# LEDs.net
KiCad netlist of a schematic drawn in Altium Designer
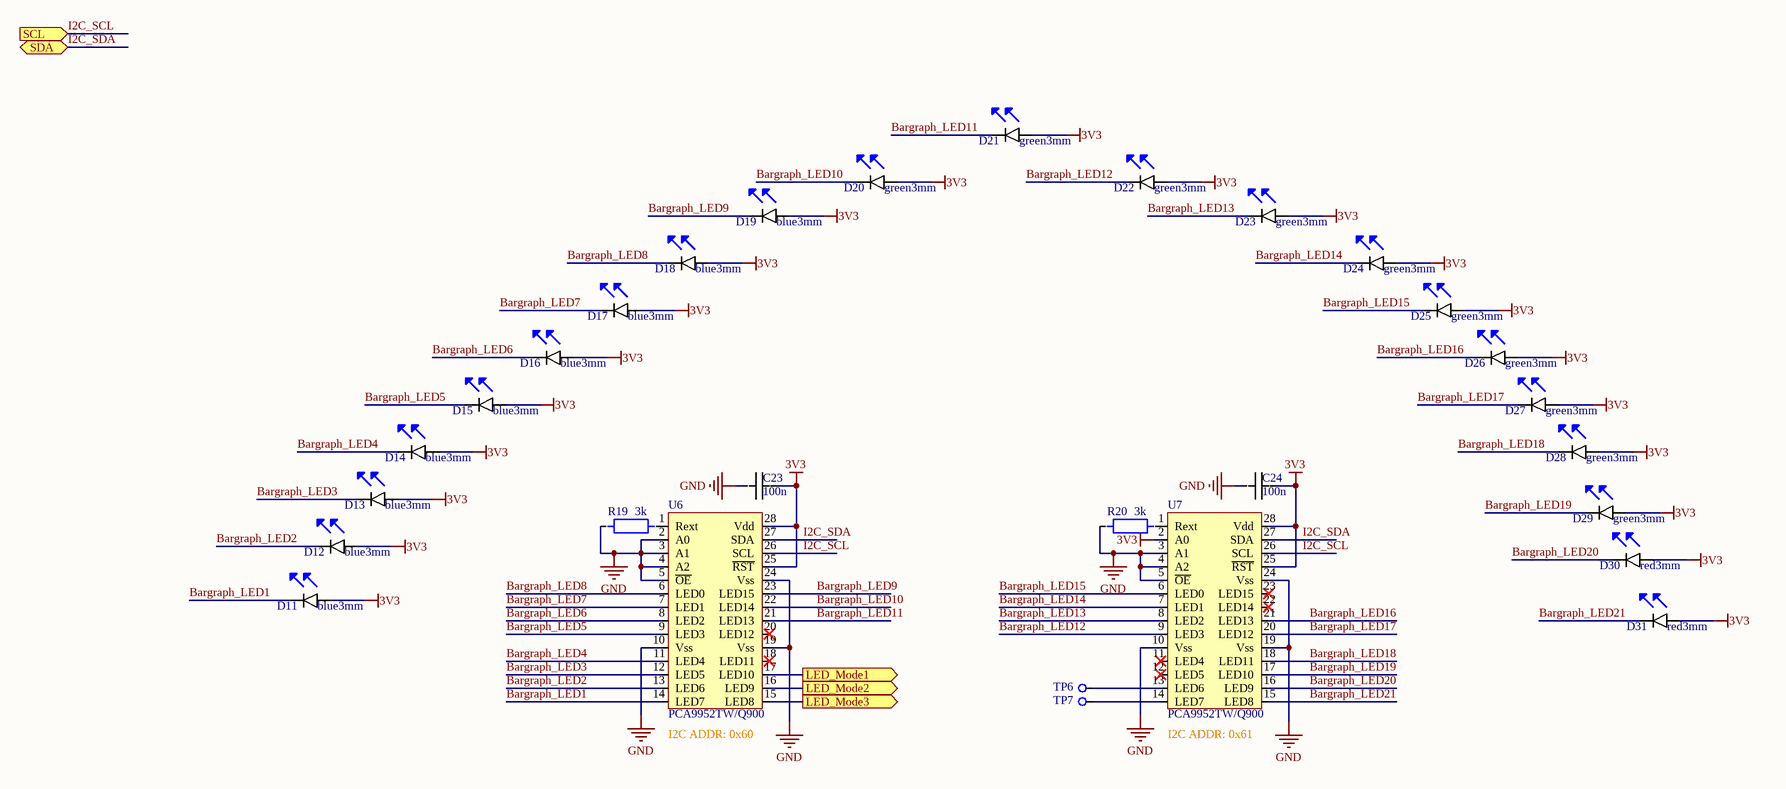
[diagram p0: LEDs.SchDoc]

(export (version "E")
  (design (tool "Eeschema 10.0.6"))
  (components
    (comp (ref "C23")
      (value "100n")
      (footprint "0402_")
      (fields
        (field (name "MANUFACTURER PARTNUM") "C1005X5R1E104K050BC")
        (field (name "MANUFACTURER") "TDK Corp")
      )
      (libsource (lib "*") (part "C"))
    )
    (comp (ref "C24")
      (value "100n")
      (footprint "0402_")
      (fields
        (field (name "MANUFACTURER PARTNUM") "C1005X5R1E104K050BC")
        (field (name "MANUFACTURER") "TDK Corp")
      )
      (libsource (lib "*") (part "C"))
    )
    (comp (ref "D11")
      (value "led")
      (footprint "LED3MM_BLUE")
      (fields
        (field (name "MANUFACTURER") "Wuerth")
        (field (name "MANUFACTURER PARTNUM") "151033BS03000")
        (field (name "COLOR_DIAM") "blue3mm")
      )
      (libsource (lib "*") (part "led"))
    )
    (comp (ref "D12")
      (value "led")
      (footprint "LED3MM_BLUE")
      (fields
        (field (name "MANUFACTURER") "Wuerth")
        (field (name "MANUFACTURER PARTNUM") "151033BS03000")
        (field (name "COLOR_DIAM") "blue3mm")
      )
      (libsource (lib "*") (part "led"))
    )
    (comp (ref "D13")
      (value "led")
      (footprint "LED3MM_BLUE")
      (fields
        (field (name "MANUFACTURER") "Wuerth")
        (field (name "MANUFACTURER PARTNUM") "151033BS03000")
        (field (name "COLOR_DIAM") "blue3mm")
      )
      (libsource (lib "*") (part "led"))
    )
    (comp (ref "D14")
      (value "led")
      (footprint "LED3MM_BLUE")
      (fields
        (field (name "MANUFACTURER") "Wuerth")
        (field (name "MANUFACTURER PARTNUM") "151033BS03000")
        (field (name "COLOR_DIAM") "blue3mm")
      )
      (libsource (lib "*") (part "led"))
    )
    (comp (ref "D15")
      (value "led")
      (footprint "LED3MM_BLUE")
      (fields
        (field (name "MANUFACTURER") "Wuerth")
        (field (name "MANUFACTURER PARTNUM") "151033BS03000")
        (field (name "COLOR_DIAM") "blue3mm")
      )
      (libsource (lib "*") (part "led"))
    )
    (comp (ref "D16")
      (value "led")
      (footprint "LED3MM_BLUE")
      (fields
        (field (name "MANUFACTURER") "Wuerth")
        (field (name "MANUFACTURER PARTNUM") "151033BS03000")
        (field (name "COLOR_DIAM") "blue3mm")
      )
      (libsource (lib "*") (part "led"))
    )
    (comp (ref "D17")
      (value "led")
      (footprint "LED3MM_BLUE")
      (fields
        (field (name "MANUFACTURER") "Wuerth")
        (field (name "MANUFACTURER PARTNUM") "151033BS03000")
        (field (name "COLOR_DIAM") "blue3mm")
      )
      (libsource (lib "*") (part "led"))
    )
    (comp (ref "D18")
      (value "led")
      (footprint "LED3MM_BLUE")
      (fields
        (field (name "MANUFACTURER") "Wuerth")
        (field (name "MANUFACTURER PARTNUM") "151033BS03000")
        (field (name "COLOR_DIAM") "blue3mm")
      )
      (libsource (lib "*") (part "led"))
    )
    (comp (ref "D19")
      (value "led")
      (footprint "LED3MM_BLUE")
      (fields
        (field (name "MANUFACTURER") "Wuerth")
        (field (name "MANUFACTURER PARTNUM") "151033BS03000")
        (field (name "COLOR_DIAM") "blue3mm")
      )
      (libsource (lib "*") (part "led"))
    )
    (comp (ref "D20")
      (value "led")
      (footprint "LED3MM_GREEN")
      (fields
        (field (name "MANUFACTURER") "Kingbright")
        (field (name "MANUFACTURER PARTNUM") "WP710A10LZGCK")
        (field (name "COLOR_DIAM") "green3mm")
      )
      (libsource (lib "*") (part "led"))
    )
    (comp (ref "D21")
      (value "led")
      (footprint "LED3MM_GREEN")
      (fields
        (field (name "MANUFACTURER") "Kingbright")
        (field (name "MANUFACTURER PARTNUM") "WP710A10LZGCK")
        (field (name "COLOR_DIAM") "green3mm")
      )
      (libsource (lib "*") (part "led"))
    )
    (comp (ref "D22")
      (value "led")
      (footprint "LED3MM_GREEN")
      (fields
        (field (name "MANUFACTURER") "Kingbright")
        (field (name "MANUFACTURER PARTNUM") "WP710A10LZGCK")
        (field (name "COLOR_DIAM") "green3mm")
      )
      (libsource (lib "*") (part "led"))
    )
    (comp (ref "D23")
      (value "led")
      (footprint "LED3MM_GREEN")
      (fields
        (field (name "MANUFACTURER") "Kingbright")
        (field (name "MANUFACTURER PARTNUM") "WP710A10LZGCK")
        (field (name "COLOR_DIAM") "green3mm")
      )
      (libsource (lib "*") (part "led"))
    )
    (comp (ref "D24")
      (value "led")
      (footprint "LED3MM_GREEN")
      (fields
        (field (name "MANUFACTURER") "Kingbright")
        (field (name "MANUFACTURER PARTNUM") "WP710A10LZGCK")
        (field (name "COLOR_DIAM") "green3mm")
      )
      (libsource (lib "*") (part "led"))
    )
    (comp (ref "D25")
      (value "led")
      (footprint "LED3MM_GREEN")
      (fields
        (field (name "MANUFACTURER") "Kingbright")
        (field (name "MANUFACTURER PARTNUM") "WP710A10LZGCK")
        (field (name "COLOR_DIAM") "green3mm")
      )
      (libsource (lib "*") (part "led"))
    )
    (comp (ref "D26")
      (value "led")
      (footprint "LED3MM_GREEN")
      (fields
        (field (name "MANUFACTURER") "Kingbright")
        (field (name "MANUFACTURER PARTNUM") "WP710A10LZGCK")
        (field (name "COLOR_DIAM") "green3mm")
      )
      (libsource (lib "*") (part "led"))
    )
    (comp (ref "D27")
      (value "led")
      (footprint "LED3MM_GREEN")
      (fields
        (field (name "MANUFACTURER") "Kingbright")
        (field (name "MANUFACTURER PARTNUM") "WP710A10LZGCK")
        (field (name "COLOR_DIAM") "green3mm")
      )
      (libsource (lib "*") (part "led"))
    )
    (comp (ref "D28")
      (value "led")
      (footprint "LED3MM_GREEN")
      (fields
        (field (name "MANUFACTURER") "Kingbright")
        (field (name "MANUFACTURER PARTNUM") "WP710A10LZGCK")
        (field (name "COLOR_DIAM") "green3mm")
      )
      (libsource (lib "*") (part "led"))
    )
    (comp (ref "D29")
      (value "led")
      (footprint "LED3MM_GREEN")
      (fields
        (field (name "MANUFACTURER") "Kingbright")
        (field (name "MANUFACTURER PARTNUM") "WP710A10LZGCK")
        (field (name "COLOR_DIAM") "green3mm")
      )
      (libsource (lib "*") (part "led"))
    )
    (comp (ref "D30")
      (value "led")
      (footprint "LED3MM_RED")
      (fields
        (field (name "MANUFACTURER") "Wuerth")
        (field (name "MANUFACTURER PARTNUM") "151033RS03000")
        (field (name "COLOR_DIAM") "red3mm")
      )
      (libsource (lib "*") (part "led"))
    )
    (comp (ref "D31")
      (value "led")
      (footprint "LED3MM_RED")
      (fields
        (field (name "MANUFACTURER") "Wuerth")
        (field (name "MANUFACTURER PARTNUM") "151033RS03000")
        (field (name "COLOR_DIAM") "red3mm")
      )
      (libsource (lib "*") (part "led"))
    )
    (comp (ref "R19")
      (value "3k")
      (footprint "0402_")
      (fields (field (name "MANUFACTURER PARTNUM") "RC0402FR-073KL") (field (name "MANUFACTURER") "Yageo"))
      (libsource (lib "*") (part "R"))
    )
    (comp (ref "R20")
      (value "3k")
      (footprint "0402_")
      (fields (field (name "MANUFACTURER PARTNUM") "RC0402FR-073KL") (field (name "MANUFACTURER") "Yageo"))
      (libsource (lib "*") (part "R"))
    )
    (comp (ref "TP6") (value "TP") (footprint "TP_PogoPin") (libsource (lib "Sch_GB_lib") (part "TP")))
    (comp (ref "TP7") (value "TP") (footprint "TP_PogoPin") (libsource (lib "Sch_GB_lib") (part "TP")))
    (comp (ref "U6")
      (value "PCA9952TW/Q900")
      (footprint "HTSSOP28")
      (fields (field (name "MANUFACTURER") "NXP") (field (name "MANUFACTURER PARTNUM") "PCA9952TW/Q900,118"))
      (libsource (lib "Sch_GB_lib") (part "PCA9952TW/Q900"))
    )
    (comp (ref "U7")
      (value "PCA9952TW/Q900")
      (footprint "HTSSOP28")
      (fields (field (name "MANUFACTURER") "NXP") (field (name "MANUFACTURER PARTNUM") "PCA9952TW/Q900,118"))
      (libsource (lib "Sch_GB_lib") (part "PCA9952TW/Q900"))
    )
  )
  (nets
    (net (code "1") (name "/Bargraph_LED1") (class "Default")
      (node (ref "D11") (pin "2") (pinfunction "2_2") (pintype "passive"))
      (node (ref "U6") (pin "14") (pinfunction "LED7_14") (pintype "passive"))
    )
    (net (code "2") (name "/Bargraph_LED2") (class "Default")
      (node (ref "D12") (pin "2") (pinfunction "2_2") (pintype "passive"))
      (node (ref "U6") (pin "13") (pinfunction "LED6_13") (pintype "passive"))
    )
    (net (code "3") (name "/Bargraph_LED3") (class "Default")
      (node (ref "D13") (pin "2") (pinfunction "2_2") (pintype "passive"))
      (node (ref "U6") (pin "12") (pinfunction "LED5_12") (pintype "passive"))
    )
    (net (code "4") (name "/Bargraph_LED4") (class "Default")
      (node (ref "D14") (pin "2") (pinfunction "2_2") (pintype "passive"))
      (node (ref "U6") (pin "11") (pinfunction "LED4_11") (pintype "passive"))
    )
    (net (code "5") (name "/Bargraph_LED5") (class "Default")
      (node (ref "D15") (pin "2") (pinfunction "2_2") (pintype "passive"))
      (node (ref "U6") (pin "9") (pinfunction "LED3_9") (pintype "passive"))
    )
    (net (code "6") (name "/Bargraph_LED6") (class "Default")
      (node (ref "D16") (pin "2") (pinfunction "2_2") (pintype "passive"))
      (node (ref "U6") (pin "8") (pinfunction "LED2_8") (pintype "passive"))
    )
    (net (code "7") (name "/Bargraph_LED7") (class "Default")
      (node (ref "D17") (pin "2") (pinfunction "2_2") (pintype "passive"))
      (node (ref "U6") (pin "7") (pinfunction "LED1_7") (pintype "passive"))
    )
    (net (code "8") (name "/Bargraph_LED8") (class "Default")
      (node (ref "D18") (pin "2") (pinfunction "2_2") (pintype "passive"))
      (node (ref "U6") (pin "6") (pinfunction "LED0_6") (pintype "passive"))
    )
    (net (code "9") (name "/Bargraph_LED9") (class "Default")
      (node (ref "D19") (pin "2") (pinfunction "2_2") (pintype "passive"))
      (node (ref "U6") (pin "23") (pinfunction "LED15_23") (pintype "passive"))
    )
    (net (code "10") (name "/Bargraph_LED10") (class "Default")
      (node (ref "D20") (pin "2") (pinfunction "2_2") (pintype "passive"))
      (node (ref "U6") (pin "22") (pinfunction "LED14_22") (pintype "passive"))
    )
    (net (code "11") (name "/Bargraph_LED11") (class "Default")
      (node (ref "D21") (pin "2") (pinfunction "2_2") (pintype "passive"))
      (node (ref "U6") (pin "21") (pinfunction "LED13_21") (pintype "passive"))
    )
    (net (code "12") (name "/Bargraph_LED12") (class "Default")
      (node (ref "D22") (pin "2") (pinfunction "2_2") (pintype "passive"))
      (node (ref "U7") (pin "9") (pinfunction "LED3_9") (pintype "passive"))
    )
    (net (code "13") (name "/Bargraph_LED13") (class "Default")
      (node (ref "D23") (pin "2") (pinfunction "2_2") (pintype "passive"))
      (node (ref "U7") (pin "8") (pinfunction "LED2_8") (pintype "passive"))
    )
    (net (code "14") (name "/Bargraph_LED14") (class "Default")
      (node (ref "D24") (pin "2") (pinfunction "2_2") (pintype "passive"))
      (node (ref "U7") (pin "7") (pinfunction "LED1_7") (pintype "passive"))
    )
    (net (code "15") (name "/Bargraph_LED15") (class "Default")
      (node (ref "D25") (pin "2") (pinfunction "2_2") (pintype "passive"))
      (node (ref "U7") (pin "6") (pinfunction "LED0_6") (pintype "passive"))
    )
    (net (code "16") (name "/Bargraph_LED16") (class "Default")
      (node (ref "D26") (pin "2") (pinfunction "2_2") (pintype "passive"))
      (node (ref "U7") (pin "21") (pinfunction "LED13_21") (pintype "passive"))
    )
    (net (code "17") (name "/Bargraph_LED17") (class "Default")
      (node (ref "D27") (pin "2") (pinfunction "2_2") (pintype "passive"))
      (node (ref "U7") (pin "20") (pinfunction "LED12_20") (pintype "passive"))
    )
    (net (code "18") (name "/Bargraph_LED18") (class "Default")
      (node (ref "D28") (pin "2") (pinfunction "2_2") (pintype "passive"))
      (node (ref "U7") (pin "18") (pinfunction "LED11_18") (pintype "passive"))
    )
    (net (code "19") (name "/Bargraph_LED19") (class "Default")
      (node (ref "D29") (pin "2") (pinfunction "2_2") (pintype "passive"))
      (node (ref "U7") (pin "17") (pinfunction "LED10_17") (pintype "passive"))
    )
    (net (code "20") (name "/Bargraph_LED20") (class "Default")
      (node (ref "D30") (pin "2") (pinfunction "2_2") (pintype "passive"))
      (node (ref "U7") (pin "16") (pinfunction "LED9_16") (pintype "passive"))
    )
    (net (code "21") (name "/Bargraph_LED21") (class "Default")
      (node (ref "D31") (pin "2") (pinfunction "2_2") (pintype "passive"))
      (node (ref "U7") (pin "15") (pinfunction "LED8_15") (pintype "passive"))
    )
    (net (code "22") (name "/I2C_SCL") (class "Default")
      (node (ref "U6") (pin "26") (pinfunction "SCL_26") (pintype "passive"))
      (node (ref "U7") (pin "26") (pinfunction "SCL_26") (pintype "passive"))
    )
    (net (code "23") (name "/I2C_SDA") (class "Default")
      (node (ref "U6") (pin "27") (pinfunction "SDA_27") (pintype "passive"))
      (node (ref "U7") (pin "27") (pinfunction "SDA_27") (pintype "passive"))
    )
    (net (code "24") (name "/LED_Mode1") (class "Default")
      (node (ref "U6") (pin "17") (pinfunction "LED10_17") (pintype "passive"))
    )
    (net (code "25") (name "/LED_Mode2") (class "Default")
      (node (ref "U6") (pin "16") (pinfunction "LED9_16") (pintype "passive"))
    )
    (net (code "26") (name "/LED_Mode3") (class "Default")
      (node (ref "U6") (pin "15") (pinfunction "LED8_15") (pintype "passive"))
    )
    (net (code "27") (name "3V3") (class "Default")
      (node (ref "C23") (pin "1") (pinfunction "1_1") (pintype "passive"))
      (node (ref "C24") (pin "1") (pinfunction "1_1") (pintype "passive"))
      (node (ref "D11") (pin "1") (pinfunction "1_1") (pintype "passive"))
      (node (ref "D12") (pin "1") (pinfunction "1_1") (pintype "passive"))
      (node (ref "D13") (pin "1") (pinfunction "1_1") (pintype "passive"))
      (node (ref "D14") (pin "1") (pinfunction "1_1") (pintype "passive"))
      (node (ref "D15") (pin "1") (pinfunction "1_1") (pintype "passive"))
      (node (ref "D16") (pin "1") (pinfunction "1_1") (pintype "passive"))
      (node (ref "D17") (pin "1") (pinfunction "1_1") (pintype "passive"))
      (node (ref "D18") (pin "1") (pinfunction "1_1") (pintype "passive"))
      (node (ref "D19") (pin "1") (pinfunction "1_1") (pintype "passive"))
      (node (ref "D20") (pin "1") (pinfunction "1_1") (pintype "passive"))
      (node (ref "D21") (pin "1") (pinfunction "1_1") (pintype "passive"))
      (node (ref "D22") (pin "1") (pinfunction "1_1") (pintype "passive"))
      (node (ref "D23") (pin "1") (pinfunction "1_1") (pintype "passive"))
      (node (ref "D24") (pin "1") (pinfunction "1_1") (pintype "passive"))
      (node (ref "D25") (pin "1") (pinfunction "1_1") (pintype "passive"))
      (node (ref "D26") (pin "1") (pinfunction "1_1") (pintype "passive"))
      (node (ref "D27") (pin "1") (pinfunction "1_1") (pintype "passive"))
      (node (ref "D28") (pin "1") (pinfunction "1_1") (pintype "passive"))
      (node (ref "D29") (pin "1") (pinfunction "1_1") (pintype "passive"))
      (node (ref "D30") (pin "1") (pinfunction "1_1") (pintype "passive"))
      (node (ref "D31") (pin "1") (pinfunction "1_1") (pintype "passive"))
      (node (ref "U6") (pin "25") (pinfunction "~{RST}_25") (pintype "passive"))
      (node (ref "U6") (pin "28") (pinfunction "Vdd_28") (pintype "passive"))
      (node (ref "U7") (pin "2") (pinfunction "A0_2") (pintype "passive"))
      (node (ref "U7") (pin "25") (pinfunction "~{RST}_25") (pintype "passive"))
      (node (ref "U7") (pin "28") (pinfunction "Vdd_28") (pintype "passive"))
    )
    (net (code "28") (name "GND") (class "Default")
      (node (ref "C23") (pin "2") (pinfunction "2_2") (pintype "passive"))
      (node (ref "C24") (pin "2") (pinfunction "2_2") (pintype "passive"))
      (node (ref "R19") (pin "1") (pinfunction "1_1") (pintype "passive"))
      (node (ref "R20") (pin "1") (pinfunction "1_1") (pintype "passive"))
      (node (ref "U6") (pin "10") (pinfunction "Vss_10") (pintype "passive"))
      (node (ref "U6") (pin "19") (pinfunction "Vss_19") (pintype "passive"))
      (node (ref "U6") (pin "2") (pinfunction "A0_2") (pintype "passive"))
      (node (ref "U6") (pin "24") (pinfunction "Vss_24") (pintype "passive"))
      (node (ref "U6") (pin "3") (pinfunction "A1_3") (pintype "passive"))
      (node (ref "U6") (pin "4") (pinfunction "A2_4") (pintype "passive"))
      (node (ref "U6") (pin "5") (pinfunction "~{OE}_5") (pintype "passive"))
      (node (ref "U7") (pin "10") (pinfunction "Vss_10") (pintype "passive"))
      (node (ref "U7") (pin "19") (pinfunction "Vss_19") (pintype "passive"))
      (node (ref "U7") (pin "24") (pinfunction "Vss_24") (pintype "passive"))
      (node (ref "U7") (pin "3") (pinfunction "A1_3") (pintype "passive"))
      (node (ref "U7") (pin "4") (pinfunction "A2_4") (pintype "passive"))
      (node (ref "U7") (pin "5") (pinfunction "~{OE}_5") (pintype "passive"))
    )
    (net (code "29") (name "Net-(U6-Rext)") (class "Default")
      (node (ref "R19") (pin "2") (pinfunction "2_2") (pintype "passive"))
      (node (ref "U6") (pin "1") (pinfunction "Rext_1") (pintype "passive"))
    )
    (net (code "30") (name "Net-(U7-LED6)") (class "Default")
      (node (ref "TP6") (pin "1") (pinfunction "1_1") (pintype "passive"))
      (node (ref "U7") (pin "13") (pinfunction "LED6_13") (pintype "passive"))
    )
    (net (code "31") (name "Net-(U7-LED7)") (class "Default")
      (node (ref "TP7") (pin "1") (pinfunction "1_1") (pintype "passive"))
      (node (ref "U7") (pin "14") (pinfunction "LED7_14") (pintype "passive"))
    )
    (net (code "32") (name "Net-(U7-Rext)") (class "Default")
      (node (ref "R20") (pin "2") (pinfunction "2_2") (pintype "passive"))
      (node (ref "U7") (pin "1") (pinfunction "Rext_1") (pintype "passive"))
    )
    (net (code "33") (name "unconnected-(U6-LED11-Pad18)") (class "Default")
      (node (ref "U6") (pin "18") (pinfunction "LED11_18") (pintype "passive+no_connect"))
    )
    (net (code "34") (name "unconnected-(U6-LED12-Pad20)") (class "Default")
      (node (ref "U6") (pin "20") (pinfunction "LED12_20") (pintype "passive+no_connect"))
    )
    (net (code "35") (name "unconnected-(U7-LED4-Pad11)") (class "Default")
      (node (ref "U7") (pin "11") (pinfunction "LED4_11") (pintype "passive+no_connect"))
    )
    (net (code "36") (name "unconnected-(U7-LED5-Pad12)") (class "Default")
      (node (ref "U7") (pin "12") (pinfunction "LED5_12") (pintype "passive+no_connect"))
    )
    (net (code "37") (name "unconnected-(U7-LED14-Pad22)") (class "Default")
      (node (ref "U7") (pin "22") (pinfunction "LED14_22") (pintype "passive+no_connect"))
    )
    (net (code "38") (name "unconnected-(U7-LED15-Pad23)") (class "Default")
      (node (ref "U7") (pin "23") (pinfunction "LED15_23") (pintype "passive+no_connect"))
    )
  )
)
